# Probe-Scope_RAM_v1_0.net
KiCad netlist of a schematic drawn in Altium Designer
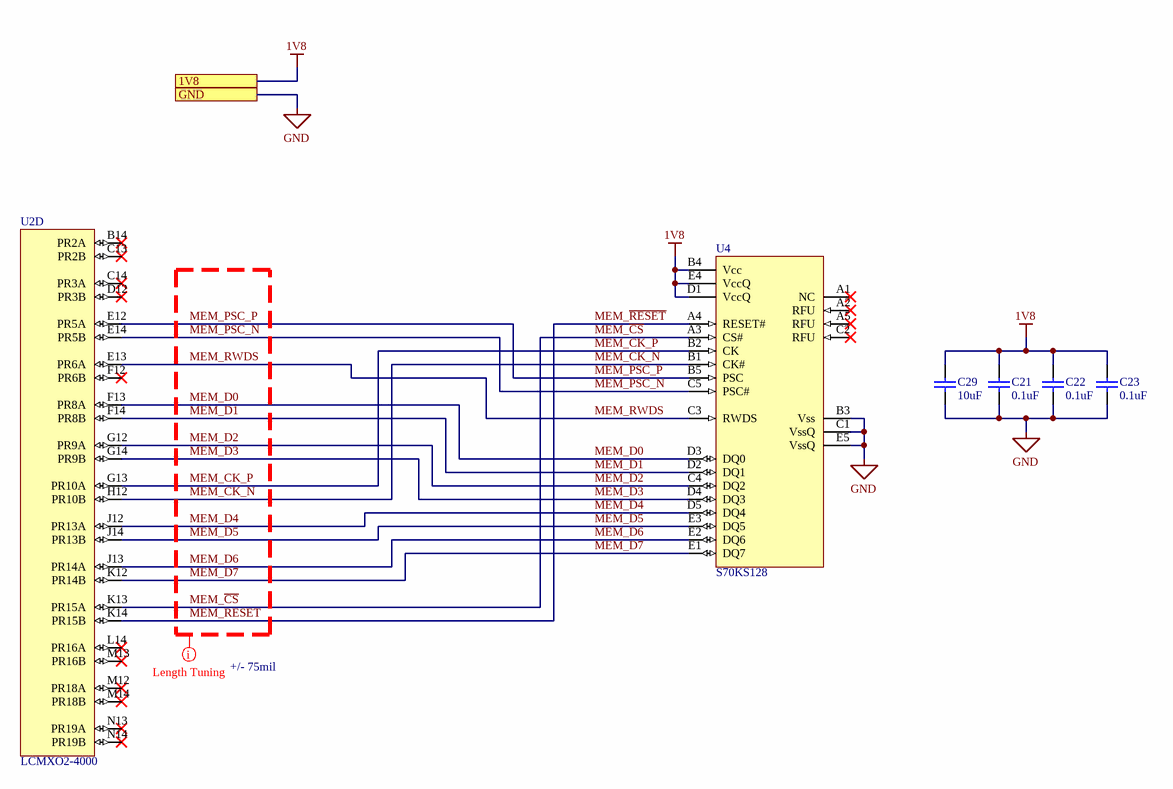
[diagram p0: Probe-Scope RAM v1.0.SchDoc]

(export (version "E")
  (design (tool "Eeschema 10.0.6"))
  (components
    (comp (ref "C21")
      (value "0.1uF")
      (footprint "0402(1005)")
      (fields
        (field (name "MANF") "Samsung Electro-Mechanics")
        (field (name "TOLERANCE") "10")
        (field (name "VOLTAGE") "6.3")
        (field (name "MODIFIED BY") "jrowley")
        (field (name "APPROVED") "False")
      )
      (libsource (lib "MENG Database Library VPN") (part "Cap"))
    )
    (comp (ref "C22")
      (value "0.1uF")
      (footprint "0402(1005)")
      (fields
        (field (name "MANF") "Samsung Electro-Mechanics")
        (field (name "TOLERANCE") "10")
        (field (name "VOLTAGE") "6.3")
        (field (name "MODIFIED BY") "jrowley")
        (field (name "APPROVED") "False")
      )
      (libsource (lib "MENG Database Library VPN") (part "Cap"))
    )
    (comp (ref "C23")
      (value "0.1uF")
      (footprint "0402(1005)")
      (fields
        (field (name "MANF") "Samsung Electro-Mechanics")
        (field (name "TOLERANCE") "10")
        (field (name "VOLTAGE") "6.3")
        (field (name "MODIFIED BY") "jrowley")
        (field (name "APPROVED") "False")
      )
      (libsource (lib "MENG Database Library VPN") (part "Cap"))
    )
    (comp (ref "C29")
      (value "10uF")
      (footprint "0603(1608)")
      (fields
        (field (name "MANF") "Samsung Electro-Mechanics")
        (field (name "TOLERANCE") "20")
        (field (name "VOLTAGE") "25")
        (field (name "MODIFIED BY") "sotterbacher")
        (field (name "APPROVED") "True")
      )
      (libsource (lib "MENG Database Library VPN") (part "Cap"))
    )
    (comp (ref "U2")
      (value "LCMXO2-4000")
      (footprint "132_Ball_csBGA_MachXO2")
      (fields (field (name "MANF") "Lattice Semiconductor"))
      (libsource (lib "PS v1.0") (part "MachXO2-4000"))
    )
    (comp (ref "U4")
      (value "S70KS128")
      (footprint "Cypress-VAA024")
      (fields (field (name "MANF") "Cypress"))
      (libsource (lib "PS") (part "S70KS"))
    )
  )
  (nets
    (net (code "1") (name "/MEM_CK_N") (class "Default")
      (node (ref "U2") (pin "H12") (pinfunction "PR10B_H12") (pintype "bidirectional"))
      (node (ref "U4") (pin "B1") (pinfunction "CK#_B1") (pintype "input"))
    )
    (net (code "2") (name "/MEM_CK_P") (class "Default")
      (node (ref "U2") (pin "G13") (pinfunction "PR10A_G13") (pintype "bidirectional"))
      (node (ref "U4") (pin "B2") (pinfunction "CK_B2") (pintype "input"))
    )
    (net (code "3") (name "/MEM_D0") (class "Default")
      (node (ref "U2") (pin "F13") (pinfunction "PR8A_F13") (pintype "bidirectional"))
      (node (ref "U4") (pin "D3") (pinfunction "DQ0_D3") (pintype "bidirectional"))
    )
    (net (code "4") (name "/MEM_D1") (class "Default")
      (node (ref "U2") (pin "F14") (pinfunction "PR8B_F14") (pintype "bidirectional"))
      (node (ref "U4") (pin "D2") (pinfunction "DQ1_D2") (pintype "bidirectional"))
    )
    (net (code "5") (name "/MEM_D2") (class "Default")
      (node (ref "U2") (pin "G12") (pinfunction "PR9A_G12") (pintype "bidirectional"))
      (node (ref "U4") (pin "C4") (pinfunction "DQ2_C4") (pintype "bidirectional"))
    )
    (net (code "6") (name "/MEM_D3") (class "Default")
      (node (ref "U2") (pin "G14") (pinfunction "PR9B_G14") (pintype "bidirectional"))
      (node (ref "U4") (pin "D4") (pinfunction "DQ3_D4") (pintype "bidirectional"))
    )
    (net (code "7") (name "/MEM_D4") (class "Default")
      (node (ref "U2") (pin "J12") (pinfunction "PR13A_J12") (pintype "bidirectional"))
      (node (ref "U4") (pin "D5") (pinfunction "DQ4_D5") (pintype "bidirectional"))
    )
    (net (code "8") (name "/MEM_D5") (class "Default")
      (node (ref "U2") (pin "J14") (pinfunction "PR13B_J14") (pintype "bidirectional"))
      (node (ref "U4") (pin "E3") (pinfunction "DQ5_E3") (pintype "bidirectional"))
    )
    (net (code "9") (name "/MEM_D6") (class "Default")
      (node (ref "U2") (pin "J13") (pinfunction "PR14A_J13") (pintype "bidirectional"))
      (node (ref "U4") (pin "E2") (pinfunction "DQ6_E2") (pintype "bidirectional"))
    )
    (net (code "10") (name "/MEM_D7") (class "Default")
      (node (ref "U2") (pin "K12") (pinfunction "PR14B_K12") (pintype "bidirectional"))
      (node (ref "U4") (pin "E1") (pinfunction "DQ7_E1") (pintype "bidirectional"))
    )
    (net (code "11") (name "/MEM_PSC_N") (class "Default")
      (node (ref "U2") (pin "E14") (pinfunction "PR5B_E14") (pintype "bidirectional"))
      (node (ref "U4") (pin "C5") (pinfunction "PSC#_C5") (pintype "input"))
    )
    (net (code "12") (name "/MEM_PSC_P") (class "Default")
      (node (ref "U2") (pin "E12") (pinfunction "PR5A_E12") (pintype "bidirectional"))
      (node (ref "U4") (pin "B5") (pinfunction "PSC_B5") (pintype "input"))
    )
    (net (code "13") (name "/MEM_RWDS") (class "Default")
      (node (ref "U2") (pin "E13") (pinfunction "PR6A_E13") (pintype "bidirectional"))
      (node (ref "U4") (pin "C3") (pinfunction "RWDS_C3") (pintype "input"))
    )
    (net (code "14") (name "/MEM_~{CS}") (class "Default")
      (node (ref "U2") (pin "K13") (pinfunction "PR15A_K13") (pintype "bidirectional"))
      (node (ref "U4") (pin "A3") (pinfunction "CS#_A3") (pintype "input"))
    )
    (net (code "15") (name "/MEM_~{RESET}") (class "Default")
      (node (ref "U2") (pin "K14") (pinfunction "PR15B_K14") (pintype "bidirectional"))
      (node (ref "U4") (pin "A4") (pinfunction "RESET#_A4") (pintype "input"))
    )
    (net (code "16") (name "1V8") (class "Default")
      (node (ref "C21") (pin "2") (pinfunction "2_2") (pintype "passive"))
      (node (ref "C22") (pin "2") (pinfunction "2_2") (pintype "passive"))
      (node (ref "C23") (pin "2") (pinfunction "2_2") (pintype "passive"))
      (node (ref "C29") (pin "2") (pinfunction "2_2") (pintype "passive"))
      (node (ref "U4") (pin "B4") (pinfunction "Vcc_B4") (pintype "power_in"))
      (node (ref "U4") (pin "D1") (pinfunction "VccQ_D1") (pintype "power_in"))
      (node (ref "U4") (pin "E4") (pinfunction "VccQ_E4") (pintype "power_in"))
    )
    (net (code "17") (name "GND") (class "Default")
      (node (ref "C21") (pin "1") (pinfunction "1_1") (pintype "passive"))
      (node (ref "C22") (pin "1") (pinfunction "1_1") (pintype "passive"))
      (node (ref "C23") (pin "1") (pinfunction "1_1") (pintype "passive"))
      (node (ref "C29") (pin "1") (pinfunction "1_1") (pintype "passive"))
      (node (ref "U4") (pin "B3") (pinfunction "Vss_B3") (pintype "power_in"))
      (node (ref "U4") (pin "C1") (pinfunction "VssQ_C1") (pintype "power_in"))
      (node (ref "U4") (pin "E5") (pinfunction "VssQ_E5") (pintype "power_in"))
    )
    (net (code "18") (name "unconnected-(U2D-PR2A-PadB14)") (class "Default")
      (node (ref "U2") (pin "B14") (pinfunction "PR2A_B14") (pintype "bidirectional+no_connect"))
    )
    (net (code "19") (name "unconnected-(U2D-PR2B-PadC13)") (class "Default")
      (node (ref "U2") (pin "C13") (pinfunction "PR2B_C13") (pintype "bidirectional+no_connect"))
    )
    (net (code "20") (name "unconnected-(U2D-PR3A-PadC14)") (class "Default")
      (node (ref "U2") (pin "C14") (pinfunction "PR3A_C14") (pintype "bidirectional+no_connect"))
    )
    (net (code "21") (name "unconnected-(U2D-PR3B-PadD12)") (class "Default")
      (node (ref "U2") (pin "D12") (pinfunction "PR3B_D12") (pintype "bidirectional+no_connect"))
    )
    (net (code "22") (name "unconnected-(U2D-PR6B-PadF12)") (class "Default")
      (node (ref "U2") (pin "F12") (pinfunction "PR6B_F12") (pintype "bidirectional+no_connect"))
    )
    (net (code "23") (name "unconnected-(U2D-PR16A-PadL14)") (class "Default")
      (node (ref "U2") (pin "L14") (pinfunction "PR16A_L14") (pintype "bidirectional+no_connect"))
    )
    (net (code "24") (name "unconnected-(U2D-PR16B-PadM13)") (class "Default")
      (node (ref "U2") (pin "M13") (pinfunction "PR16B_M13") (pintype "bidirectional+no_connect"))
    )
    (net (code "25") (name "unconnected-(U2D-PR18A-PadM12)") (class "Default")
      (node (ref "U2") (pin "M12") (pinfunction "PR18A_M12") (pintype "bidirectional+no_connect"))
    )
    (net (code "26") (name "unconnected-(U2D-PR18B-PadM14)") (class "Default")
      (node (ref "U2") (pin "M14") (pinfunction "PR18B_M14") (pintype "bidirectional+no_connect"))
    )
    (net (code "27") (name "unconnected-(U2D-PR19A-PadN13)") (class "Default")
      (node (ref "U2") (pin "N13") (pinfunction "PR19A_N13") (pintype "bidirectional+no_connect"))
    )
    (net (code "28") (name "unconnected-(U2D-PR19B-PadN14)") (class "Default")
      (node (ref "U2") (pin "N14") (pinfunction "PR19B_N14") (pintype "bidirectional+no_connect"))
    )
    (net (code "29") (name "unconnected-(U4-NC-PadA1)") (class "Default")
      (node (ref "U4") (pin "A1") (pinfunction "NC_A1") (pintype "passive+no_connect"))
    )
    (net (code "30") (name "unconnected-(U4-RFU-PadA2)") (class "Default")
      (node (ref "U4") (pin "A2") (pinfunction "RFU_A2") (pintype "input+no_connect"))
    )
    (net (code "31") (name "unconnected-(U4-RFU-PadA5)") (class "Default")
      (node (ref "U4") (pin "A5") (pinfunction "RFU_A5") (pintype "input+no_connect"))
    )
    (net (code "32") (name "unconnected-(U4-RFU-PadC2)") (class "Default")
      (node (ref "U4") (pin "C2") (pinfunction "RFU_C2") (pintype "input+no_connect"))
    )
  )
)
